# track_voltage_v1_2.net
KiCad netlist of a schematic drawn in EAGLE
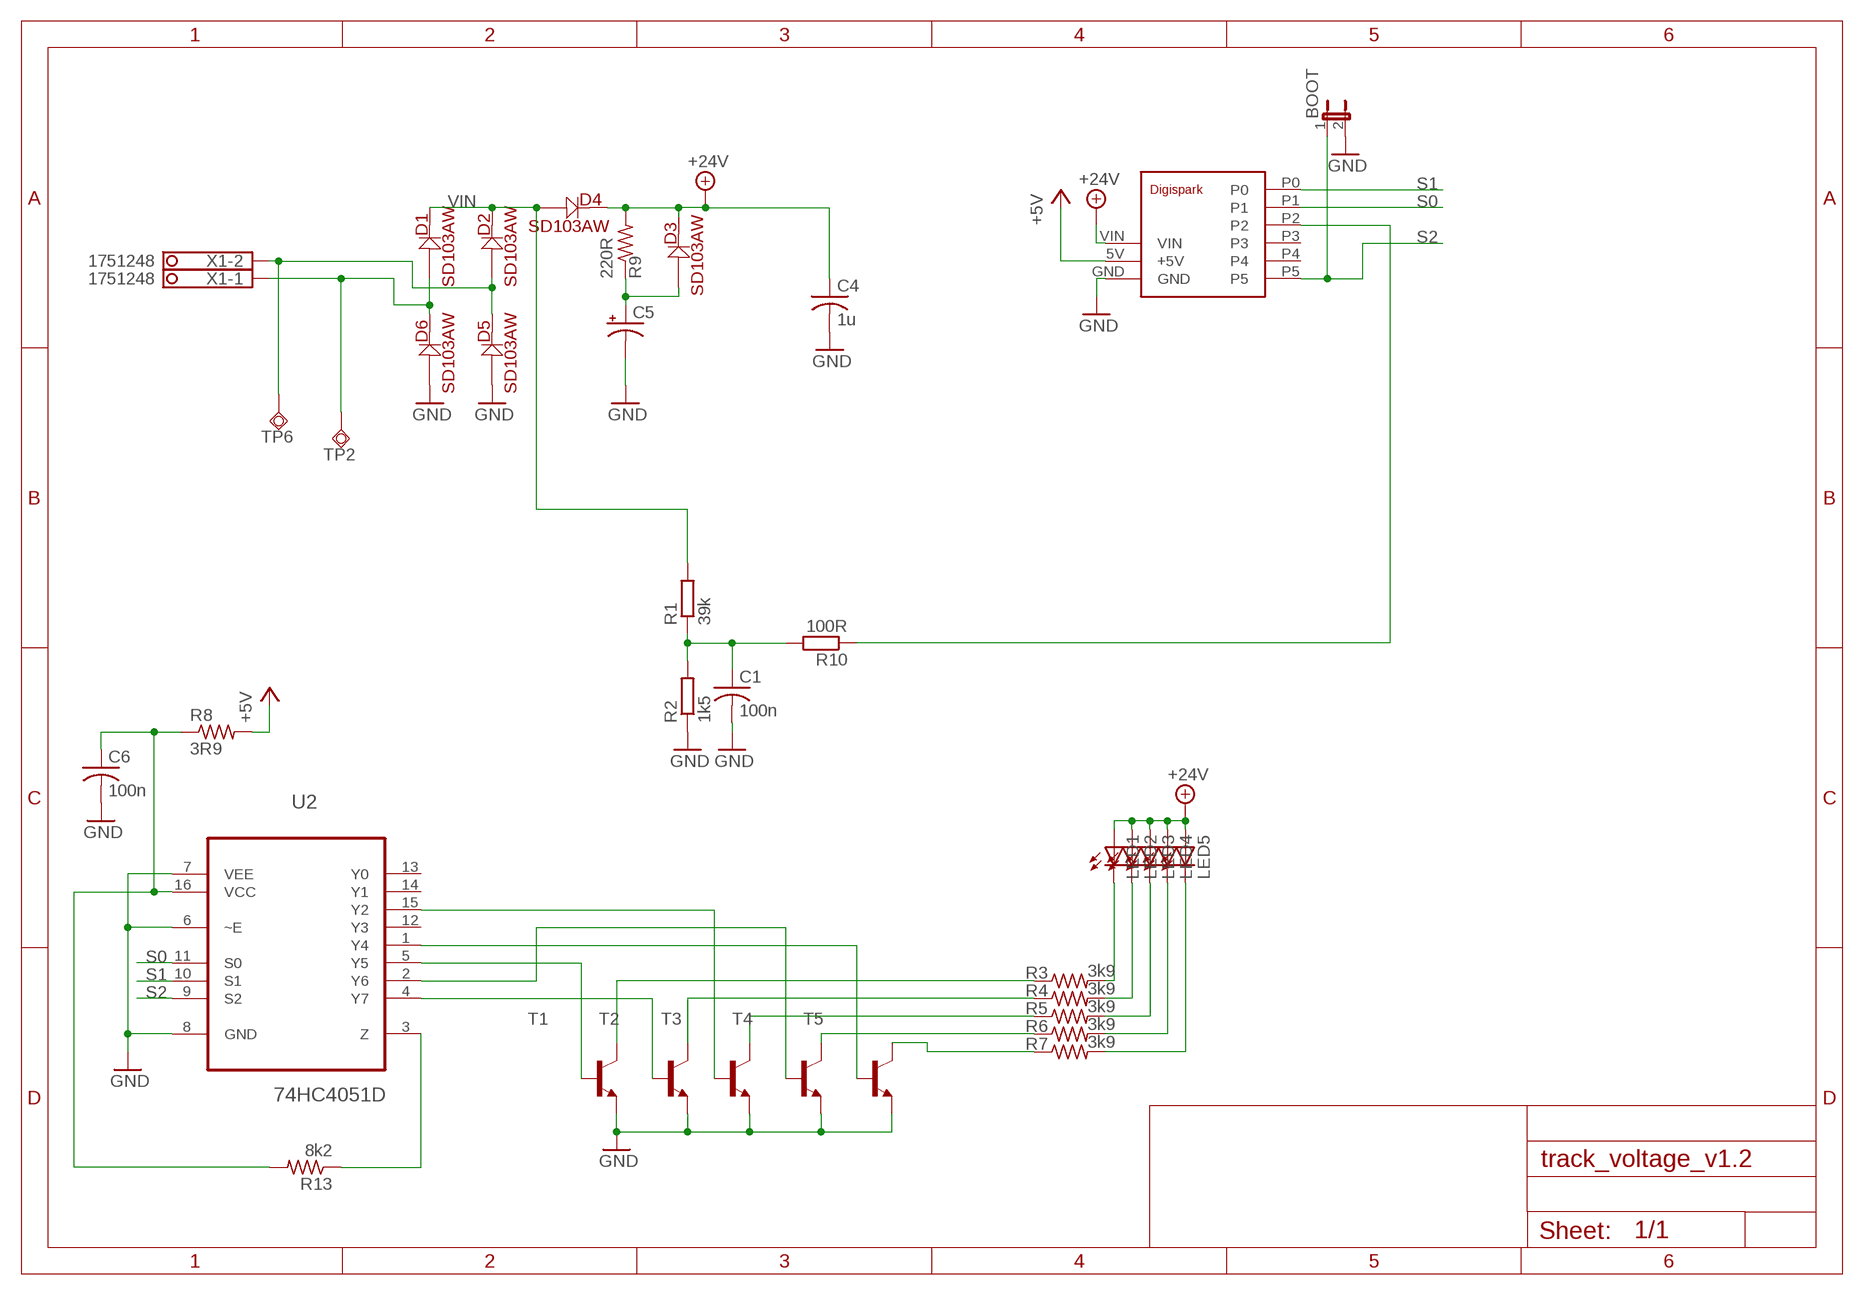
[diagram p0: schematic, sheet 1]

(export (version "E")
  (design (tool "Eeschema 10.0.6"))
  (components
    (comp (ref "BOOT")
      (value "JP1E")
      (footprint "eagle-import:JP1")
      (libsource (lib "eagle-import") (part "JP1E"))
    )
    (comp (ref "C1")
      (value "100n")
      (footprint "eagle-import:C0603")
      (libsource (lib "eagle-import") (part "C-USC0603"))
    )
    (comp (ref "C4")
      (value "1u")
      (footprint "eagle-import:C0603")
      (libsource (lib "eagle-import") (part "C-USC0603"))
    )
    (comp (ref "C5")
      (value "CPOL-USE3.5-10")
      (footprint "eagle-import:E3,5-10")
      (libsource (lib "eagle-import") (part "CPOL-USE3.5-10"))
    )
    (comp (ref "C6")
      (value "100n")
      (footprint "eagle-import:C0603")
      (libsource (lib "eagle-import") (part "C-USC0603"))
    )
    (comp (ref "D1")
      (value "SD103AW")
      (footprint "eagle-import:SOD-123")
      (libsource (lib "eagle-import") (part "SD103AW"))
    )
    (comp (ref "D2")
      (value "SD103AW")
      (footprint "eagle-import:SOD-123")
      (libsource (lib "eagle-import") (part "SD103AW"))
    )
    (comp (ref "D3")
      (value "SD103AW")
      (footprint "eagle-import:SOD-123")
      (libsource (lib "eagle-import") (part "SD103AW"))
    )
    (comp (ref "D4")
      (value "SD103AW")
      (footprint "eagle-import:SOD-123")
      (libsource (lib "eagle-import") (part "SD103AW"))
    )
    (comp (ref "D5")
      (value "SD103AW")
      (footprint "eagle-import:SOD-123")
      (libsource (lib "eagle-import") (part "SD103AW"))
    )
    (comp (ref "D6")
      (value "SD103AW")
      (footprint "eagle-import:SOD-123")
      (libsource (lib "eagle-import") (part "SD103AW"))
    )
    (comp (ref "LED1")
      (value "LED3MM")
      (footprint "eagle-import:LED3MM")
      (libsource (lib "eagle-import") (part "LED3MM"))
    )
    (comp (ref "LED2")
      (value "LED3MM")
      (footprint "eagle-import:LED3MM")
      (libsource (lib "eagle-import") (part "LED3MM"))
    )
    (comp (ref "LED3")
      (value "LED3MM")
      (footprint "eagle-import:LED3MM")
      (libsource (lib "eagle-import") (part "LED3MM"))
    )
    (comp (ref "LED4")
      (value "LED3MM")
      (footprint "eagle-import:LED3MM")
      (libsource (lib "eagle-import") (part "LED3MM"))
    )
    (comp (ref "LED5")
      (value "LED3MM")
      (footprint "eagle-import:LED3MM")
      (libsource (lib "eagle-import") (part "LED3MM"))
    )
    (comp (ref "R1")
      (value "39k")
      (footprint "eagle-import:R0603")
      (libsource (lib "eagle-import") (part "R-EU_R0603"))
    )
    (comp (ref "R2")
      (value "1k5")
      (footprint "eagle-import:R0603")
      (libsource (lib "eagle-import") (part "R-EU_R0603"))
    )
    (comp (ref "R3")
      (value "3k9")
      (footprint "eagle-import:R0805")
      (libsource (lib "eagle-import") (part "R-US_R0805"))
    )
    (comp (ref "R4")
      (value "3k9")
      (footprint "eagle-import:R0805")
      (libsource (lib "eagle-import") (part "R-US_R0805"))
    )
    (comp (ref "R5")
      (value "3k9")
      (footprint "eagle-import:R0805")
      (libsource (lib "eagle-import") (part "R-US_R0805"))
    )
    (comp (ref "R6")
      (value "3k9")
      (footprint "eagle-import:R0805")
      (libsource (lib "eagle-import") (part "R-US_R0805"))
    )
    (comp (ref "R7")
      (value "3k9")
      (footprint "eagle-import:R0805")
      (libsource (lib "eagle-import") (part "R-US_R0805"))
    )
    (comp (ref "R8")
      (value "3R9")
      (footprint "eagle-import:R1206")
      (libsource (lib "eagle-import") (part "R-US_R1206"))
    )
    (comp (ref "R9")
      (value "220R")
      (footprint "eagle-import:R0805")
      (libsource (lib "eagle-import") (part "R-US_R0805"))
    )
    (comp (ref "R10")
      (value "100R")
      (footprint "eagle-import:R0603")
      (libsource (lib "eagle-import") (part "R-EU_R0603"))
    )
    (comp (ref "R13")
      (value "8k2")
      (footprint "eagle-import:R0603")
      (libsource (lib "eagle-import") (part "R-US_R0603"))
    )
    (comp (ref "T1")
      (value "BC817-16-NPN-SOT23-BEC")
      (footprint "eagle-import:SOT23-BEC")
      (libsource (lib "eagle-import") (part "-NPN-SOT23-BECBC817-16"))
    )
    (comp (ref "T2")
      (value "BC817-16-NPN-SOT23-BEC")
      (footprint "eagle-import:SOT23-BEC")
      (libsource (lib "eagle-import") (part "-NPN-SOT23-BECBC817-16"))
    )
    (comp (ref "T3")
      (value "BC817-16-NPN-SOT23-BEC")
      (footprint "eagle-import:SOT23-BEC")
      (libsource (lib "eagle-import") (part "-NPN-SOT23-BECBC817-16"))
    )
    (comp (ref "T4")
      (value "BC817-16-NPN-SOT23-BEC")
      (footprint "eagle-import:SOT23-BEC")
      (libsource (lib "eagle-import") (part "-NPN-SOT23-BECBC817-16"))
    )
    (comp (ref "T5")
      (value "BC817-16-NPN-SOT23-BEC")
      (footprint "eagle-import:SOT23-BEC")
      (libsource (lib "eagle-import") (part "-NPN-SOT23-BECBC817-16"))
    )
    (comp (ref "TP2")
      (value "TPSQTP20SQ")
      (footprint "eagle-import:TP20SQ")
      (libsource (lib "eagle-import") (part "TPSQTP20SQ"))
    )
    (comp (ref "TP6")
      (value "TPSQTP20SQ")
      (footprint "eagle-import:TP20SQ")
      (libsource (lib "eagle-import") (part "TPSQTP20SQ"))
    )
    (comp (ref "U$2")
      (value "DIGISPARK")
      (footprint "eagle-import:DIGISPARK_78M05")
      (libsource (lib "eagle-import") (part "DIGISPARK"))
    )
    (comp (ref "U2")
      (value "74HC4051D")
      (footprint "eagle-import:SOIC127P600X175-16N")
      (fields (field (name "MF") "Toshiba Semiconductor"))
      (libsource (lib "eagle-import") (part "74HC4051D"))
    )
    (comp (ref "X1")
      (value "1751248")
      (footprint "eagle-import:1751248")
      (libsource (lib "eagle-import") (part "1751248"))
    )
  )
  (nets
    (net (code "1") (name "+5V") (class "Default")
      (node (ref "R8") (pin "2") (pinfunction "2_2") (pintype "passive"))
      (node (ref "U$2") (pin "5V") (pinfunction "+5V_5V") (pintype "bidirectional"))
    )
    (net (code "2") (name "+24V") (class "Default")
      (node (ref "C4") (pin "1") (pinfunction "1_1") (pintype "passive"))
      (node (ref "D3") (pin "-") (pinfunction "-_-") (pintype "bidirectional"))
      (node (ref "D4") (pin "-") (pinfunction "-_-") (pintype "bidirectional"))
      (node (ref "LED1") (pin "A") (pinfunction "A_A") (pintype "passive"))
      (node (ref "LED2") (pin "A") (pinfunction "A_A") (pintype "passive"))
      (node (ref "LED3") (pin "A") (pinfunction "A_A") (pintype "passive"))
      (node (ref "LED4") (pin "A") (pinfunction "A_A") (pintype "passive"))
      (node (ref "LED5") (pin "A") (pinfunction "A_A") (pintype "passive"))
      (node (ref "R9") (pin "2") (pinfunction "2_2") (pintype "passive"))
      (node (ref "U$2") (pin "VIN") (pinfunction "VIN_VIN") (pintype "bidirectional"))
    )
    (net (code "3") (name "/S0") (class "Default")
      (node (ref "U$2") (pin "P1") (pinfunction "P1_P1") (pintype "bidirectional"))
      (node (ref "U2") (pin "11") (pinfunction "S0_11") (pintype "input"))
    )
    (net (code "4") (name "/S1") (class "Default")
      (node (ref "U$2") (pin "P0") (pinfunction "P0_P0") (pintype "bidirectional"))
      (node (ref "U2") (pin "10") (pinfunction "S1_10") (pintype "input"))
    )
    (net (code "5") (name "/S2") (class "Default")
      (node (ref "BOOT") (pin "1") (pinfunction "1_1") (pintype "passive"))
      (node (ref "U$2") (pin "P5") (pinfunction "P5_P5") (pintype "bidirectional"))
      (node (ref "U2") (pin "9") (pinfunction "S2_9") (pintype "input"))
    )
    (net (code "6") (name "/VIN") (class "Default")
      (node (ref "D1") (pin "-") (pinfunction "-_-") (pintype "bidirectional"))
      (node (ref "D2") (pin "-") (pinfunction "-_-") (pintype "bidirectional"))
      (node (ref "D4") (pin "+") (pinfunction "+_+") (pintype "bidirectional"))
      (node (ref "R1") (pin "2") (pinfunction "2_2") (pintype "passive"))
    )
    (net (code "7") (name "GND") (class "Default")
      (node (ref "BOOT") (pin "2") (pinfunction "2_2") (pintype "passive"))
      (node (ref "C1") (pin "2") (pinfunction "2_2") (pintype "passive"))
      (node (ref "C4") (pin "2") (pinfunction "2_2") (pintype "passive"))
      (node (ref "C5") (pin "-") (pinfunction "-_-") (pintype "passive"))
      (node (ref "C6") (pin "2") (pinfunction "2_2") (pintype "passive"))
      (node (ref "D5") (pin "+") (pinfunction "+_+") (pintype "bidirectional"))
      (node (ref "D6") (pin "+") (pinfunction "+_+") (pintype "bidirectional"))
      (node (ref "R2") (pin "1") (pinfunction "1_1") (pintype "passive"))
      (node (ref "T1") (pin "E") (pinfunction "E_E") (pintype "passive"))
      (node (ref "T2") (pin "E") (pinfunction "E_E") (pintype "passive"))
      (node (ref "T3") (pin "E") (pinfunction "E_E") (pintype "passive"))
      (node (ref "T4") (pin "E") (pinfunction "E_E") (pintype "passive"))
      (node (ref "T5") (pin "E") (pinfunction "E_E") (pintype "passive"))
      (node (ref "U$2") (pin "GND") (pinfunction "GND_GND") (pintype "bidirectional"))
      (node (ref "U2") (pin "6") (pinfunction "~{E}_6") (pintype "input"))
      (node (ref "U2") (pin "7") (pinfunction "VEE_7") (pintype "power_in"))
      (node (ref "U2") (pin "8") (pinfunction "GND_8") (pintype "passive"))
    )
    (net (code "8") (name "Net-(C1-Pad1)") (class "Default")
      (node (ref "C1") (pin "1") (pinfunction "1_1") (pintype "passive"))
      (node (ref "R1") (pin "1") (pinfunction "1_1") (pintype "passive"))
      (node (ref "R10") (pin "2") (pinfunction "2_2") (pintype "passive"))
      (node (ref "R2") (pin "2") (pinfunction "2_2") (pintype "passive"))
    )
    (net (code "9") (name "Net-(C5-Pad+)") (class "Default")
      (node (ref "C5") (pin "+") (pinfunction "+_+") (pintype "passive"))
      (node (ref "D3") (pin "+") (pinfunction "+_+") (pintype "bidirectional"))
      (node (ref "R9") (pin "1") (pinfunction "1_1") (pintype "passive"))
    )
    (net (code "10") (name "Net-(LED1-C)") (class "Default")
      (node (ref "LED1") (pin "K") (pinfunction "C_K") (pintype "passive"))
      (node (ref "R3") (pin "2") (pinfunction "2_2") (pintype "passive"))
    )
    (net (code "11") (name "Net-(LED2-C)") (class "Default")
      (node (ref "LED2") (pin "K") (pinfunction "C_K") (pintype "passive"))
      (node (ref "R4") (pin "2") (pinfunction "2_2") (pintype "passive"))
    )
    (net (code "12") (name "Net-(LED3-C)") (class "Default")
      (node (ref "LED3") (pin "K") (pinfunction "C_K") (pintype "passive"))
      (node (ref "R5") (pin "2") (pinfunction "2_2") (pintype "passive"))
    )
    (net (code "13") (name "Net-(LED4-C)") (class "Default")
      (node (ref "LED4") (pin "K") (pinfunction "C_K") (pintype "passive"))
      (node (ref "R6") (pin "2") (pinfunction "2_2") (pintype "passive"))
    )
    (net (code "14") (name "Net-(LED5-C)") (class "Default")
      (node (ref "LED5") (pin "K") (pinfunction "C_K") (pintype "passive"))
      (node (ref "R7") (pin "2") (pinfunction "2_2") (pintype "passive"))
    )
    (net (code "15") (name "Net-(R3-Pad1)") (class "Default")
      (node (ref "R3") (pin "1") (pinfunction "1_1") (pintype "passive"))
      (node (ref "T1") (pin "C") (pinfunction "C_C") (pintype "passive"))
    )
    (net (code "16") (name "Net-(R4-Pad1)") (class "Default")
      (node (ref "R4") (pin "1") (pinfunction "1_1") (pintype "passive"))
      (node (ref "T2") (pin "C") (pinfunction "C_C") (pintype "passive"))
    )
    (net (code "17") (name "Net-(R5-Pad1)") (class "Default")
      (node (ref "R5") (pin "1") (pinfunction "1_1") (pintype "passive"))
      (node (ref "T3") (pin "C") (pinfunction "C_C") (pintype "passive"))
    )
    (net (code "18") (name "Net-(R6-Pad1)") (class "Default")
      (node (ref "R6") (pin "1") (pinfunction "1_1") (pintype "passive"))
      (node (ref "T4") (pin "C") (pinfunction "C_C") (pintype "passive"))
    )
    (net (code "19") (name "Net-(R7-Pad1)") (class "Default")
      (node (ref "R7") (pin "1") (pinfunction "1_1") (pintype "passive"))
      (node (ref "T5") (pin "C") (pinfunction "C_C") (pintype "passive"))
    )
    (net (code "20") (name "Net-(R10-Pad1)") (class "Default")
      (node (ref "R10") (pin "1") (pinfunction "1_1") (pintype "passive"))
      (node (ref "U$2") (pin "P2") (pinfunction "P2_P2") (pintype "bidirectional"))
    )
    (net (code "21") (name "Net-(U2-VCC)") (class "Default")
      (node (ref "C6") (pin "1") (pinfunction "1_1") (pintype "passive"))
      (node (ref "R13") (pin "2") (pinfunction "2_2") (pintype "passive"))
      (node (ref "R8") (pin "1") (pinfunction "1_1") (pintype "passive"))
      (node (ref "U2") (pin "16") (pinfunction "VCC_16") (pintype "power_in"))
    )
    (net (code "22") (name "Net-(U2-Y2)") (class "Default")
      (node (ref "T3") (pin "B") (pinfunction "B_B") (pintype "passive"))
      (node (ref "U2") (pin "15") (pinfunction "Y2_15") (pintype "bidirectional"))
    )
    (net (code "23") (name "Net-(U2-Y4)") (class "Default")
      (node (ref "T5") (pin "B") (pinfunction "B_B") (pintype "passive"))
      (node (ref "U2") (pin "1") (pinfunction "Y4_1") (pintype "bidirectional"))
    )
    (net (code "24") (name "Net-(U2-Y5)") (class "Default")
      (node (ref "T1") (pin "B") (pinfunction "B_B") (pintype "passive"))
      (node (ref "U2") (pin "5") (pinfunction "Y5_5") (pintype "bidirectional"))
    )
    (net (code "25") (name "Net-(U2-Y6)") (class "Default")
      (node (ref "T4") (pin "B") (pinfunction "B_B") (pintype "passive"))
      (node (ref "U2") (pin "2") (pinfunction "Y6_2") (pintype "bidirectional"))
    )
    (net (code "26") (name "Net-(U2-Y7)") (class "Default")
      (node (ref "T2") (pin "B") (pinfunction "B_B") (pintype "passive"))
      (node (ref "U2") (pin "4") (pinfunction "Y7_4") (pintype "bidirectional"))
    )
    (net (code "27") (name "Net-(U2-Z)") (class "Default")
      (node (ref "R13") (pin "1") (pinfunction "1_1") (pintype "passive"))
      (node (ref "U2") (pin "3") (pinfunction "Z_3") (pintype "bidirectional"))
    )
    (net (code "28") (name "Net-(X1A-K)") (class "Default")
      (node (ref "D1") (pin "+") (pinfunction "+_+") (pintype "bidirectional"))
      (node (ref "D6") (pin "-") (pinfunction "-_-") (pintype "bidirectional"))
      (node (ref "TP2") (pin "TP") (pinfunction "TP_TP") (pintype "input"))
      (node (ref "X1") (pin "1") (pinfunction "K_1") (pintype "passive"))
    )
    (net (code "29") (name "Net-(X1B-K)") (class "Default")
      (node (ref "D2") (pin "+") (pinfunction "+_+") (pintype "bidirectional"))
      (node (ref "D5") (pin "-") (pinfunction "-_-") (pintype "bidirectional"))
      (node (ref "TP6") (pin "TP") (pinfunction "TP_TP") (pintype "input"))
      (node (ref "X1") (pin "2") (pinfunction "K_2") (pintype "passive"))
    )
    (net (code "30") (name "unconnected-(U$2-PadP3)") (class "Default")
      (node (ref "U$2") (pin "P3") (pinfunction "P3_P3") (pintype "bidirectional"))
    )
    (net (code "31") (name "unconnected-(U$2-PadP4)") (class "Default")
      (node (ref "U$2") (pin "P4") (pinfunction "P4_P4") (pintype "bidirectional"))
    )
    (net (code "32") (name "unconnected-(U2-Y0-Pad13)") (class "Default")
      (node (ref "U2") (pin "13") (pinfunction "Y0_13") (pintype "bidirectional"))
    )
    (net (code "33") (name "unconnected-(U2-Y1-Pad14)") (class "Default")
      (node (ref "U2") (pin "14") (pinfunction "Y1_14") (pintype "bidirectional"))
    )
    (net (code "34") (name "unconnected-(U2-Y3-Pad12)") (class "Default")
      (node (ref "U2") (pin "12") (pinfunction "Y3_12") (pintype "bidirectional"))
    )
  )
)
